# cluster2.net
KiCad netlist of a schematic drawn in EAGLE
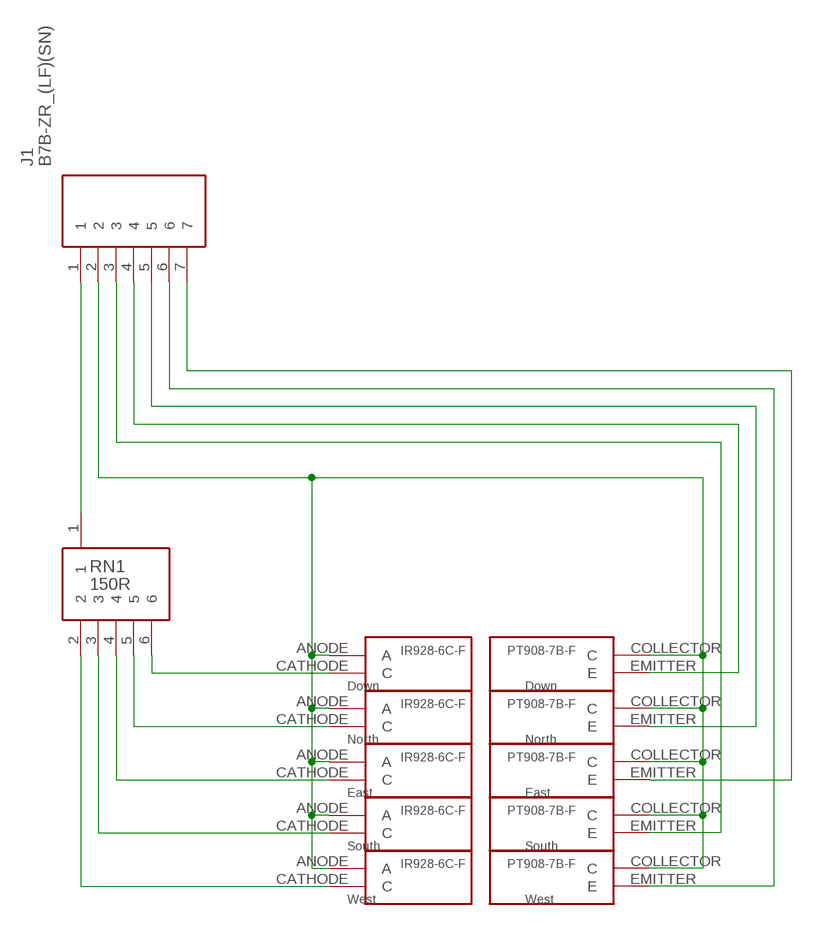
[diagram p0: schematic, sheet 1]

(export (version "E")
  (design (tool "Eeschema 10.0.6"))
  (components
    (comp (ref "J1")
      (value "B7B-ZR_(LF)(SN)")
      (footprint "eagle-import:SHDR7W50P0X150_1X7_1200X350X45")
      (fields
        (field (name "MANUFACTURER_PART_NUMBER") "B7B-ZR (LF)(SN)")
        (field (name "RS_PART_NUMBER") "7620828")
      )
      (libsource (lib "eagle-import") (part "B7B-ZR_(LF)(SN)"))
    )
    (comp (ref "LED1")
      (value "Down")
      (footprint "eagle-import:IR928-6C-F")
      (libsource (lib "eagle-import") (part "IR928-6C-F"))
    )
    (comp (ref "LED2")
      (value "North")
      (footprint "eagle-import:IR928-6C-F")
      (libsource (lib "eagle-import") (part "IR928-6C-F"))
    )
    (comp (ref "LED3")
      (value "East")
      (footprint "eagle-import:IR928-6C-F")
      (libsource (lib "eagle-import") (part "IR928-6C-F"))
    )
    (comp (ref "LED4")
      (value "South")
      (footprint "eagle-import:IR928-6C-F")
      (libsource (lib "eagle-import") (part "IR928-6C-F"))
    )
    (comp (ref "LED5")
      (value "West")
      (footprint "eagle-import:IR928-6C-F")
      (libsource (lib "eagle-import") (part "IR928-6C-F"))
    )
    (comp (ref "PT1")
      (value "Down")
      (footprint "eagle-import:PT908-7B-F")
      (libsource (lib "eagle-import") (part "PT908-7B-F"))
    )
    (comp (ref "PT2")
      (value "North")
      (footprint "eagle-import:PT908-7B-F")
      (libsource (lib "eagle-import") (part "PT908-7B-F"))
    )
    (comp (ref "PT3")
      (value "East")
      (footprint "eagle-import:PT908-7B-F")
      (libsource (lib "eagle-import") (part "PT908-7B-F"))
    )
    (comp (ref "PT4")
      (value "South")
      (footprint "eagle-import:PT908-7B-F")
      (libsource (lib "eagle-import") (part "PT908-7B-F"))
    )
    (comp (ref "PT5")
      (value "West")
      (footprint "eagle-import:PT908-7B-F")
      (libsource (lib "eagle-import") (part "PT908-7B-F"))
    )
    (comp (ref "RN1")
      (value "150R")
      (footprint "eagle-import:6PIN-RESISTOR-NETWORK")
      (libsource (lib "eagle-import") (part "6PIN-RESISTOR-NETWORK6PIN-RESISTOR-NETWORK"))
    )
  )
  (nets
    (net (code "1") (name "Net-(J1-Pad1)") (class "Default")
      (node (ref "J1") (pin "1") (pinfunction "1_1") (pintype "bidirectional"))
      (node (ref "RN1") (pin "1") (pinfunction "1_1") (pintype "bidirectional"))
    )
    (net (code "2") (name "Net-(LED1-A)") (class "Default")
      (node (ref "J1") (pin "2") (pinfunction "2_2") (pintype "bidirectional"))
      (node (ref "LED1") (pin "ANODE") (pinfunction "A_ANODE") (pintype "input"))
      (node (ref "LED2") (pin "ANODE") (pinfunction "A_ANODE") (pintype "input"))
      (node (ref "LED3") (pin "ANODE") (pinfunction "A_ANODE") (pintype "input"))
      (node (ref "LED4") (pin "ANODE") (pinfunction "A_ANODE") (pintype "input"))
      (node (ref "LED5") (pin "ANODE") (pinfunction "A_ANODE") (pintype "input"))
      (node (ref "PT1") (pin "COLLECTOR") (pinfunction "C_COLLECTOR") (pintype "input"))
      (node (ref "PT2") (pin "COLLECTOR") (pinfunction "C_COLLECTOR") (pintype "input"))
      (node (ref "PT3") (pin "COLLECTOR") (pinfunction "C_COLLECTOR") (pintype "input"))
      (node (ref "PT4") (pin "COLLECTOR") (pinfunction "C_COLLECTOR") (pintype "input"))
      (node (ref "PT5") (pin "COLLECTOR") (pinfunction "C_COLLECTOR") (pintype "input"))
    )
    (net (code "3") (name "Net-(LED1-C)") (class "Default")
      (node (ref "LED1") (pin "CATHODE") (pinfunction "C_CATHODE") (pintype "output"))
      (node (ref "RN1") (pin "6") (pinfunction "6_6") (pintype "bidirectional"))
    )
    (net (code "4") (name "Net-(LED2-C)") (class "Default")
      (node (ref "LED2") (pin "CATHODE") (pinfunction "C_CATHODE") (pintype "output"))
      (node (ref "RN1") (pin "5") (pinfunction "5_5") (pintype "bidirectional"))
    )
    (net (code "5") (name "Net-(LED3-C)") (class "Default")
      (node (ref "LED3") (pin "CATHODE") (pinfunction "C_CATHODE") (pintype "output"))
      (node (ref "RN1") (pin "4") (pinfunction "4_4") (pintype "bidirectional"))
    )
    (net (code "6") (name "Net-(LED4-C)") (class "Default")
      (node (ref "LED4") (pin "CATHODE") (pinfunction "C_CATHODE") (pintype "output"))
      (node (ref "RN1") (pin "3") (pinfunction "3_3") (pintype "bidirectional"))
    )
    (net (code "7") (name "Net-(LED5-C)") (class "Default")
      (node (ref "LED5") (pin "CATHODE") (pinfunction "C_CATHODE") (pintype "output"))
      (node (ref "RN1") (pin "2") (pinfunction "2_2") (pintype "bidirectional"))
    )
    (net (code "8") (name "Net-(PT1-E)") (class "Default")
      (node (ref "J1") (pin "4") (pinfunction "4_4") (pintype "bidirectional"))
      (node (ref "PT1") (pin "EMITTER") (pinfunction "E_EMITTER") (pintype "output"))
    )
    (net (code "9") (name "Net-(PT2-E)") (class "Default")
      (node (ref "J1") (pin "5") (pinfunction "5_5") (pintype "bidirectional"))
      (node (ref "PT2") (pin "EMITTER") (pinfunction "E_EMITTER") (pintype "output"))
    )
    (net (code "10") (name "Net-(PT3-E)") (class "Default")
      (node (ref "J1") (pin "7") (pinfunction "7_7") (pintype "bidirectional"))
      (node (ref "PT3") (pin "EMITTER") (pinfunction "E_EMITTER") (pintype "output"))
    )
    (net (code "11") (name "Net-(PT4-E)") (class "Default")
      (node (ref "J1") (pin "3") (pinfunction "3_3") (pintype "bidirectional"))
      (node (ref "PT4") (pin "EMITTER") (pinfunction "E_EMITTER") (pintype "output"))
    )
    (net (code "12") (name "Net-(PT5-E)") (class "Default")
      (node (ref "J1") (pin "6") (pinfunction "6_6") (pintype "bidirectional"))
      (node (ref "PT5") (pin "EMITTER") (pinfunction "E_EMITTER") (pintype "output"))
    )
  )
)
